# RPi_UART-USB_Shim.net
KiCad netlist of a schematic drawn in EAGLE
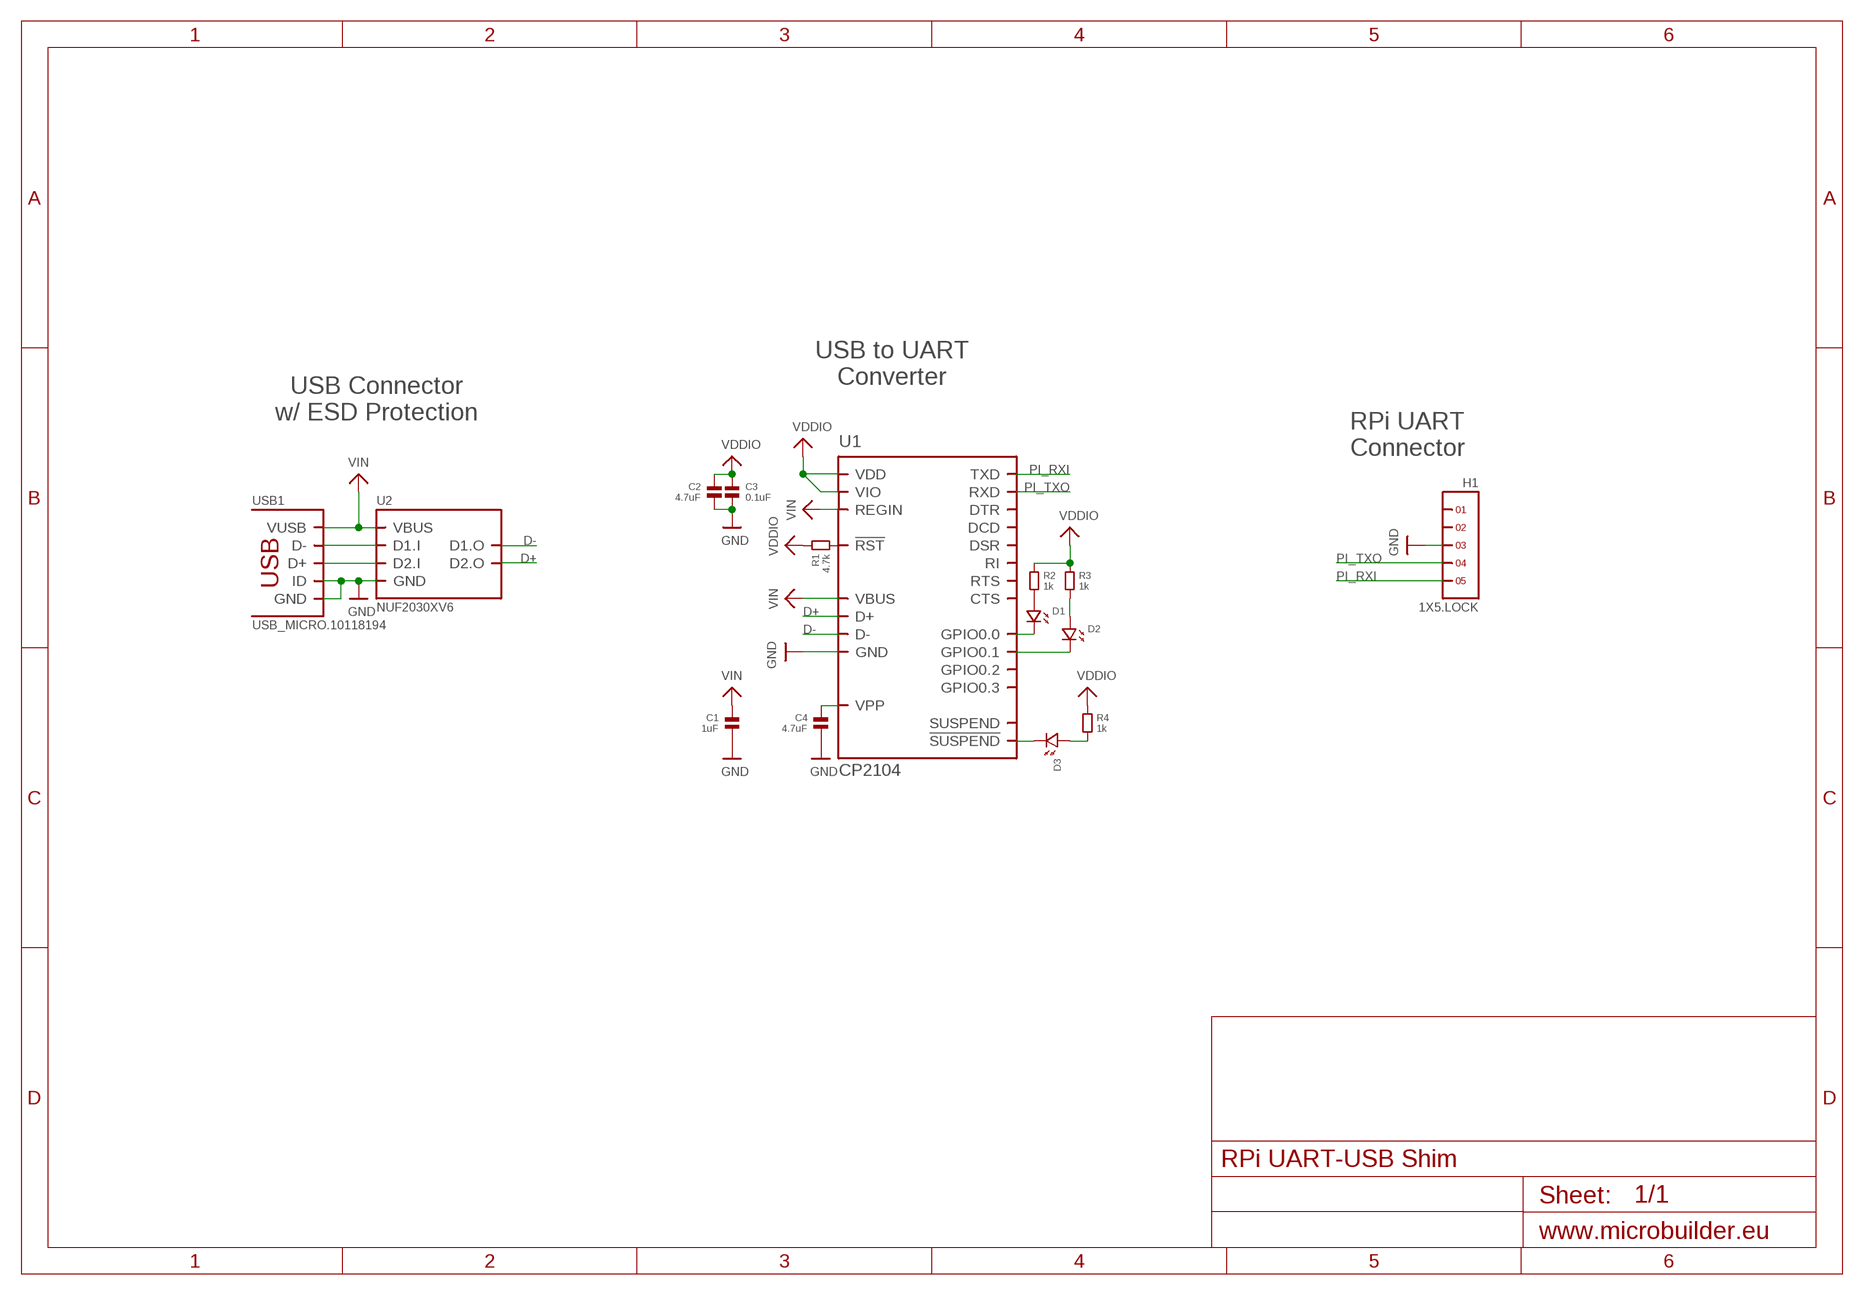
[diagram p0: schematic, sheet 1]

(export (version "E")
  (design (tool "Eeschema 10.0.6"))
  (components
    (comp (ref "C1")
      (value "1uF")
      (footprint "eagle-import:0402")
      (libsource (lib "eagle-import") (part "CAPACITOR.0402"))
    )
    (comp (ref "C2")
      (value "4.7uF")
      (footprint "eagle-import:0402")
      (libsource (lib "eagle-import") (part "CAPACITOR.0402"))
    )
    (comp (ref "C3")
      (value "0.1uF")
      (footprint "eagle-import:0402")
      (libsource (lib "eagle-import") (part "CAPACITOR.0402"))
    )
    (comp (ref "C4")
      (value "4.7uF")
      (footprint "eagle-import:0402")
      (libsource (lib "eagle-import") (part "CAPACITOR.0402"))
    )
    (comp (ref "D1")
      (value "LED.0402")
      (footprint "eagle-import:0402.LED")
      (libsource (lib "eagle-import") (part "LED.0402"))
    )
    (comp (ref "D2")
      (value "LED.0402")
      (footprint "eagle-import:0402.LED")
      (libsource (lib "eagle-import") (part "LED.0402"))
    )
    (comp (ref "D3")
      (value "LED.0402")
      (footprint "eagle-import:0402.LED")
      (libsource (lib "eagle-import") (part "LED.0402"))
    )
    (comp (ref "H1")
      (value "1X5.LOCK")
      (footprint "eagle-import:1X5.LOCK")
      (libsource (lib "eagle-import") (part "1X5.LOCK"))
    )
    (comp (ref "R1")
      (value "4.7k")
      (footprint "eagle-import:0402")
      (libsource (lib "eagle-import") (part "RESISTOR.0402"))
    )
    (comp (ref "R2")
      (value "1k")
      (footprint "eagle-import:0402")
      (libsource (lib "eagle-import") (part "RESISTOR.0402"))
    )
    (comp (ref "R3")
      (value "1k")
      (footprint "eagle-import:0402")
      (libsource (lib "eagle-import") (part "RESISTOR.0402"))
    )
    (comp (ref "R4")
      (value "1k")
      (footprint "eagle-import:0402")
      (libsource (lib "eagle-import") (part "RESISTOR.0402"))
    )
    (comp (ref "U1")
      (value "CP2104")
      (footprint "eagle-import:QFN24")
      (libsource (lib "eagle-import") (part "CP2104"))
    )
    (comp (ref "U2")
      (value "NUF2030XV6")
      (footprint "eagle-import:SOT-563")
      (libsource (lib "eagle-import") (part "NUF2030XV6"))
    )
    (comp (ref "USB1")
      (value "USB_MICRO.10118194")
      (footprint "eagle-import:10118194")
      (libsource (lib "eagle-import") (part "USB_MICRO.10118194"))
    )
  )
  (nets
    (net (code "1") (name "/D+") (class "Default")
      (node (ref "U1") (pin "3") (pinfunction "D+_3") (pintype "bidirectional"))
      (node (ref "U2") (pin "4") (pinfunction "D2.O_4") (pintype "bidirectional"))
    )
    (net (code "2") (name "/D-") (class "Default")
      (node (ref "U1") (pin "4") (pinfunction "D-_4") (pintype "bidirectional"))
      (node (ref "U2") (pin "6") (pinfunction "D1.O_6") (pintype "bidirectional"))
    )
    (net (code "3") (name "/PI_RXI") (class "Default")
      (node (ref "H1") (pin "5") (pinfunction "5_5") (pintype "bidirectional"))
      (node (ref "U1") (pin "21") (pinfunction "TXD_21") (pintype "bidirectional"))
    )
    (net (code "4") (name "/PI_TXO") (class "Default")
      (node (ref "H1") (pin "4") (pinfunction "4_4") (pintype "bidirectional"))
      (node (ref "U1") (pin "20") (pinfunction "RXD_20") (pintype "bidirectional"))
    )
    (net (code "5") (name "GND") (class "Default")
      (node (ref "C1") (pin "2") (pinfunction "2_2") (pintype "bidirectional"))
      (node (ref "C2") (pin "2") (pinfunction "2_2") (pintype "bidirectional"))
      (node (ref "C3") (pin "2") (pinfunction "2_2") (pintype "bidirectional"))
      (node (ref "C4") (pin "2") (pinfunction "2_2") (pintype "bidirectional"))
      (node (ref "H1") (pin "3") (pinfunction "3_3") (pintype "bidirectional"))
      (node (ref "U1") (pin "2") (pinfunction "GND_2") (pintype "bidirectional"))
      (node (ref "U1") (pin "PAD") (pinfunction "GND_PAD") (pintype "bidirectional"))
      (node (ref "U2") (pin "2") (pinfunction "GND_2") (pintype "bidirectional"))
      (node (ref "USB1") (pin "4") (pinfunction "ID_4") (pintype "bidirectional"))
      (node (ref "USB1") (pin "5") (pinfunction "GND_5") (pintype "bidirectional"))
      (node (ref "USB1") (pin "PAD@1") (pinfunction "GND_PAD@1") (pintype "bidirectional"))
      (node (ref "USB1") (pin "PAD@10") (pinfunction "GND_PAD@10") (pintype "bidirectional"))
      (node (ref "USB1") (pin "PAD@11") (pinfunction "GND_PAD@11") (pintype "bidirectional"))
      (node (ref "USB1") (pin "PAD@12") (pinfunction "GND_PAD@12") (pintype "bidirectional"))
      (node (ref "USB1") (pin "PAD@13") (pinfunction "GND_PAD@13") (pintype "bidirectional"))
      (node (ref "USB1") (pin "PAD@14") (pinfunction "GND_PAD@14") (pintype "bidirectional"))
      (node (ref "USB1") (pin "PAD@15") (pinfunction "GND_PAD@15") (pintype "bidirectional"))
      (node (ref "USB1") (pin "PAD@16") (pinfunction "GND_PAD@16") (pintype "bidirectional"))
      (node (ref "USB1") (pin "PAD@2") (pinfunction "GND_PAD@2") (pintype "bidirectional"))
      (node (ref "USB1") (pin "PAD@3") (pinfunction "GND_PAD@3") (pintype "bidirectional"))
      (node (ref "USB1") (pin "PAD@4") (pinfunction "GND_PAD@4") (pintype "bidirectional"))
      (node (ref "USB1") (pin "PAD@5") (pinfunction "GND_PAD@5") (pintype "bidirectional"))
      (node (ref "USB1") (pin "PAD@6") (pinfunction "GND_PAD@6") (pintype "bidirectional"))
      (node (ref "USB1") (pin "PAD@7") (pinfunction "GND_PAD@7") (pintype "bidirectional"))
      (node (ref "USB1") (pin "PAD@8") (pinfunction "GND_PAD@8") (pintype "bidirectional"))
      (node (ref "USB1") (pin "PAD@9") (pinfunction "GND_PAD@9") (pintype "bidirectional"))
    )
    (net (code "6") (name "Net-(D1-1)") (class "Default")
      (node (ref "D1") (pin "P$1") (pinfunction "1_P$1") (pintype "bidirectional"))
      (node (ref "R2") (pin "2") (pinfunction "2_2") (pintype "bidirectional"))
    )
    (net (code "7") (name "Net-(D1-2)") (class "Default")
      (node (ref "D1") (pin "P$2") (pinfunction "2_P$2") (pintype "bidirectional"))
      (node (ref "U1") (pin "14") (pinfunction "GPIO0.0_14") (pintype "bidirectional"))
    )
    (net (code "8") (name "Net-(D2-1)") (class "Default")
      (node (ref "D2") (pin "P$1") (pinfunction "1_P$1") (pintype "bidirectional"))
      (node (ref "R3") (pin "2") (pinfunction "2_2") (pintype "bidirectional"))
    )
    (net (code "9") (name "Net-(D2-2)") (class "Default")
      (node (ref "D2") (pin "P$2") (pinfunction "2_P$2") (pintype "bidirectional"))
      (node (ref "U1") (pin "13") (pinfunction "GPIO0.1_13") (pintype "bidirectional"))
    )
    (net (code "10") (name "Net-(D3-1)") (class "Default")
      (node (ref "D3") (pin "P$1") (pinfunction "1_P$1") (pintype "bidirectional"))
      (node (ref "R4") (pin "2") (pinfunction "2_2") (pintype "bidirectional"))
    )
    (net (code "11") (name "Net-(D3-2)") (class "Default")
      (node (ref "D3") (pin "P$2") (pinfunction "2_P$2") (pintype "bidirectional"))
      (node (ref "U1") (pin "15") (pinfunction "~{SUSPEND}_15") (pintype "bidirectional"))
    )
    (net (code "12") (name "Net-(U1-VPP)") (class "Default")
      (node (ref "C4") (pin "1") (pinfunction "1_1") (pintype "bidirectional"))
      (node (ref "U1") (pin "16") (pinfunction "VPP_16") (pintype "bidirectional"))
    )
    (net (code "13") (name "Net-(U1-~{RST})") (class "Default")
      (node (ref "R1") (pin "2") (pinfunction "2_2") (pintype "bidirectional"))
      (node (ref "U1") (pin "9") (pinfunction "~{RST}_9") (pintype "bidirectional"))
    )
    (net (code "14") (name "Net-(U2-D1.I)") (class "Default")
      (node (ref "U2") (pin "1") (pinfunction "D1.I_1") (pintype "bidirectional"))
      (node (ref "USB1") (pin "2") (pinfunction "D-_2") (pintype "bidirectional"))
    )
    (net (code "15") (name "Net-(U2-D2.I)") (class "Default")
      (node (ref "U2") (pin "3") (pinfunction "D2.I_3") (pintype "bidirectional"))
      (node (ref "USB1") (pin "3") (pinfunction "D+_3") (pintype "bidirectional"))
    )
    (net (code "16") (name "VDDIO") (class "Default")
      (node (ref "C2") (pin "1") (pinfunction "1_1") (pintype "bidirectional"))
      (node (ref "C3") (pin "1") (pinfunction "1_1") (pintype "bidirectional"))
      (node (ref "R1") (pin "1") (pinfunction "1_1") (pintype "bidirectional"))
      (node (ref "R2") (pin "1") (pinfunction "1_1") (pintype "bidirectional"))
      (node (ref "R3") (pin "1") (pinfunction "1_1") (pintype "bidirectional"))
      (node (ref "R4") (pin "1") (pinfunction "1_1") (pintype "bidirectional"))
      (node (ref "U1") (pin "5") (pinfunction "VIO_5") (pintype "bidirectional"))
      (node (ref "U1") (pin "6") (pinfunction "VDD_6") (pintype "bidirectional"))
    )
    (net (code "17") (name "VIN") (class "Default")
      (node (ref "C1") (pin "1") (pinfunction "1_1") (pintype "bidirectional"))
      (node (ref "U1") (pin "7") (pinfunction "REGIN_7") (pintype "bidirectional"))
      (node (ref "U1") (pin "8") (pinfunction "VBUS_8") (pintype "bidirectional"))
      (node (ref "U2") (pin "5") (pinfunction "VBUS_5") (pintype "bidirectional"))
      (node (ref "USB1") (pin "1") (pinfunction "VUSB_1") (pintype "bidirectional"))
    )
    (net (code "18") (name "unconnected-(H1-Pad1)") (class "Default")
      (node (ref "H1") (pin "1") (pinfunction "1_1") (pintype "bidirectional"))
    )
    (net (code "19") (name "unconnected-(H1-Pad2)") (class "Default")
      (node (ref "H1") (pin "2") (pinfunction "2_2") (pintype "bidirectional"))
    )
    (net (code "20") (name "unconnected-(U1-CTS-Pad18)") (class "Default")
      (node (ref "U1") (pin "18") (pinfunction "CTS_18") (pintype "bidirectional"))
    )
    (net (code "21") (name "unconnected-(U1-DCD-Pad24)") (class "Default")
      (node (ref "U1") (pin "24") (pinfunction "DCD_24") (pintype "bidirectional"))
    )
    (net (code "22") (name "unconnected-(U1-DSR-Pad22)") (class "Default")
      (node (ref "U1") (pin "22") (pinfunction "DSR_22") (pintype "bidirectional"))
    )
    (net (code "23") (name "unconnected-(U1-DTR-Pad23)") (class "Default")
      (node (ref "U1") (pin "23") (pinfunction "DTR_23") (pintype "bidirectional"))
    )
    (net (code "24") (name "unconnected-(U1-GPIO0.2-Pad12)") (class "Default")
      (node (ref "U1") (pin "12") (pinfunction "GPIO0.2_12") (pintype "bidirectional"))
    )
    (net (code "25") (name "unconnected-(U1-GPIO0.3-Pad11)") (class "Default")
      (node (ref "U1") (pin "11") (pinfunction "GPIO0.3_11") (pintype "bidirectional"))
    )
    (net (code "26") (name "unconnected-(U1-RI-Pad1)") (class "Default")
      (node (ref "U1") (pin "1") (pinfunction "RI_1") (pintype "bidirectional"))
    )
    (net (code "27") (name "unconnected-(U1-RTS-Pad19)") (class "Default")
      (node (ref "U1") (pin "19") (pinfunction "RTS_19") (pintype "bidirectional"))
    )
    (net (code "28") (name "unconnected-(U1-SUSPEND-Pad17)") (class "Default")
      (node (ref "U1") (pin "17") (pinfunction "SUSPEND_17") (pintype "bidirectional"))
    )
  )
)
